# Power-V1_0.net
KiCad netlist of a schematic drawn in Altium Designer
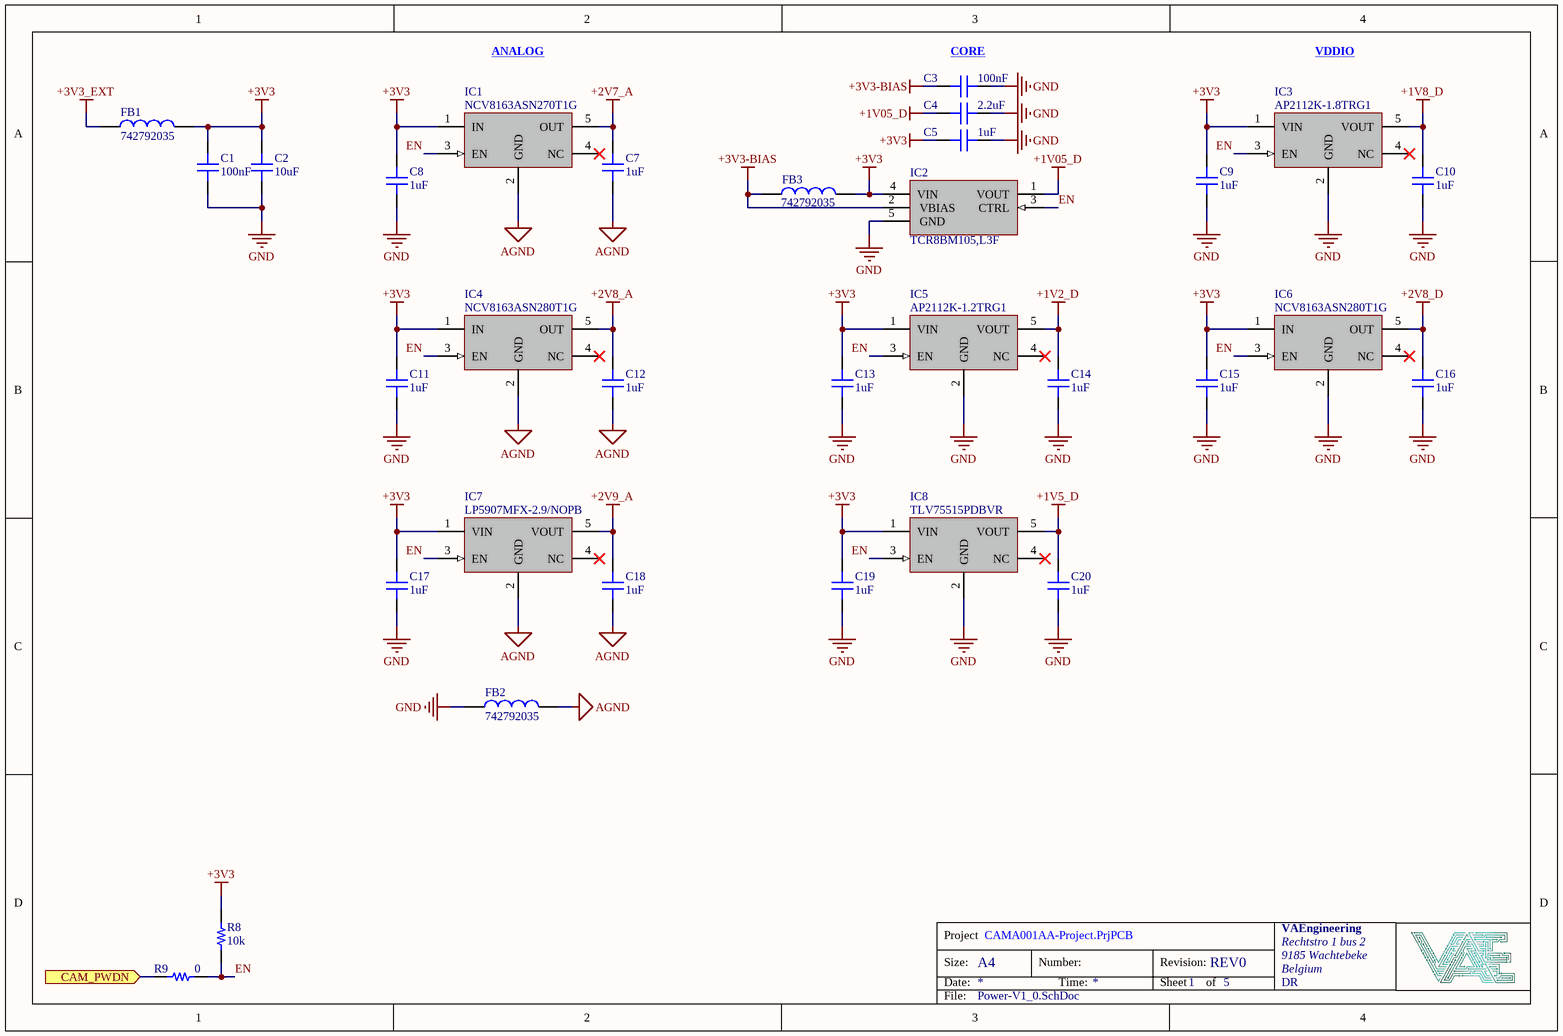
[diagram p0: Power-V1_0.SchDoc]

(export (version "E")
  (design (tool "Eeschema 10.0.6"))
  (components
    (comp (ref "C1")
      (value "CL10B104KB8NNNL")
      (footprint "Esmart C0603")
      (description "CL10 Series 0603 0.1 uF 50 V ±10% Tolerance X7R Multilayer Ceramic Capacitor")
      (fields
        (field (name "MANUFACTURER") "Samsung")
        (field (name "TOLERANCE") "10%")
        (field (name "CAPACITANCE") "100nF")
      )
      (libsource (lib "Passives") (part "Samsung CL10B104KB8NNNL"))
    )
    (comp (ref "C2")
      (value "CL21A106KOQNNWE")
      (footprint "ESmart C0805")
      (description "CAP CER 10UF 16V X5R 0805")
      (fields
        (field (name "MANUFACTURER") "Samsung")
        (field (name "TOLERANCE") "10%")
        (field (name "CAPACITANCE") "10uF")
      )
      (libsource (lib "Passives") (part "Sasmung CL21A106KOQNNWE"))
    )
    (comp (ref "C3")
      (value "CL10B104KB8NNNL")
      (footprint "Esmart C0603")
      (description "CL10 Series 0603 0.1 uF 50 V ±10% Tolerance X7R Multilayer Ceramic Capacitor")
      (fields
        (field (name "MANUFACTURER") "Samsung")
        (field (name "TOLERANCE") "10%")
        (field (name "CAPACITANCE") "100nF")
      )
      (libsource (lib "Passives") (part "Samsung CL10B104KB8NNNL"))
    )
    (comp (ref "C4")
      (value "LMK107B7225KA-TR")
      (footprint "ESMART C0603")
      (description "0603 2.2 uF 10 V ±10 % Tolerance X7R Surface Mount Multilayer Ceramic Capacitor")
      (fields
        (field (name "MANUFACTURER") "Taiyo Yuden")
        (field (name "TOLERANCE") "10%")
        (field (name "CAPACITANCE") "2.2uF")
      )
      (libsource (lib "Passives") (part "Taiyo Yuden LMK107B7225KA-TR"))
    )
    (comp (ref "C5")
      (value "CL10A105KB8NNNC")
      (footprint "ESmart C0603 - Samsung")
      (description "Cap Ceramic 1uF 50V X5R 10% SMD 0603 85C Cardboard T/R")
      (fields
        (field (name "MANUFACTURER") "Samsung")
        (field (name "TOLERANCE") "10%")
        (field (name "CAPACITANCE") "1uF")
      )
      (libsource (lib "Passives") (part "Samsung CL10A105KB8NNNC"))
    )
    (comp (ref "C7")
      (value "CL10A105KB8NNNC")
      (footprint "ESmart C0603 - Samsung")
      (description "Cap Ceramic 1uF 50V X5R 10% SMD 0603 85C Cardboard T/R")
      (fields
        (field (name "MANUFACTURER") "Samsung")
        (field (name "TOLERANCE") "10%")
        (field (name "CAPACITANCE") "1uF")
      )
      (libsource (lib "Passives") (part "Samsung CL10A105KB8NNNC"))
    )
    (comp (ref "C8")
      (value "CL10A105KB8NNNC")
      (footprint "ESmart C0603 - Samsung")
      (description "Cap Ceramic 1uF 50V X5R 10% SMD 0603 85C Cardboard T/R")
      (fields
        (field (name "MANUFACTURER") "Samsung")
        (field (name "TOLERANCE") "10%")
        (field (name "CAPACITANCE") "1uF")
      )
      (libsource (lib "Passives") (part "Samsung CL10A105KB8NNNC"))
    )
    (comp (ref "C9")
      (value "CL10A105KB8NNNC")
      (footprint "ESmart C0603 - Samsung")
      (description "Cap Ceramic 1uF 50V X5R 10% SMD 0603 85C Cardboard T/R")
      (fields
        (field (name "MANUFACTURER") "Samsung")
        (field (name "TOLERANCE") "10%")
        (field (name "CAPACITANCE") "1uF")
      )
      (libsource (lib "Passives") (part "Samsung CL10A105KB8NNNC"))
    )
    (comp (ref "C10")
      (value "CL10A105KB8NNNC")
      (footprint "ESmart C0603 - Samsung")
      (description "Cap Ceramic 1uF 50V X5R 10% SMD 0603 85C Cardboard T/R")
      (fields
        (field (name "MANUFACTURER") "Samsung")
        (field (name "TOLERANCE") "10%")
        (field (name "CAPACITANCE") "1uF")
      )
      (libsource (lib "Passives") (part "Samsung CL10A105KB8NNNC"))
    )
    (comp (ref "C11")
      (value "CL10A105KB8NNNC")
      (footprint "ESmart C0603 - Samsung")
      (description "Cap Ceramic 1uF 50V X5R 10% SMD 0603 85C Cardboard T/R")
      (fields
        (field (name "MANUFACTURER") "Samsung")
        (field (name "TOLERANCE") "10%")
        (field (name "CAPACITANCE") "1uF")
      )
      (libsource (lib "Passives") (part "Samsung CL10A105KB8NNNC"))
    )
    (comp (ref "C12")
      (value "CL10A105KB8NNNC")
      (footprint "ESmart C0603 - Samsung")
      (description "Cap Ceramic 1uF 50V X5R 10% SMD 0603 85C Cardboard T/R")
      (fields
        (field (name "MANUFACTURER") "Samsung")
        (field (name "TOLERANCE") "10%")
        (field (name "CAPACITANCE") "1uF")
      )
      (libsource (lib "Passives") (part "Samsung CL10A105KB8NNNC"))
    )
    (comp (ref "C13")
      (value "CL10A105KB8NNNC")
      (footprint "ESmart C0603 - Samsung")
      (description "Cap Ceramic 1uF 50V X5R 10% SMD 0603 85C Cardboard T/R")
      (fields
        (field (name "MANUFACTURER") "Samsung")
        (field (name "TOLERANCE") "10%")
        (field (name "CAPACITANCE") "1uF")
      )
      (libsource (lib "Passives") (part "Samsung CL10A105KB8NNNC"))
    )
    (comp (ref "C14")
      (value "CL10A105KB8NNNC")
      (footprint "ESmart C0603 - Samsung")
      (description "Cap Ceramic 1uF 50V X5R 10% SMD 0603 85C Cardboard T/R")
      (fields
        (field (name "MANUFACTURER") "Samsung")
        (field (name "TOLERANCE") "10%")
        (field (name "CAPACITANCE") "1uF")
      )
      (libsource (lib "Passives") (part "Samsung CL10A105KB8NNNC"))
    )
    (comp (ref "C15")
      (value "CL10A105KB8NNNC")
      (footprint "ESmart C0603 - Samsung")
      (description "Cap Ceramic 1uF 50V X5R 10% SMD 0603 85C Cardboard T/R")
      (fields
        (field (name "MANUFACTURER") "Samsung")
        (field (name "TOLERANCE") "10%")
        (field (name "CAPACITANCE") "1uF")
      )
      (libsource (lib "Passives") (part "Samsung CL10A105KB8NNNC"))
    )
    (comp (ref "C16")
      (value "CL10A105KB8NNNC")
      (footprint "ESmart C0603 - Samsung")
      (description "Cap Ceramic 1uF 50V X5R 10% SMD 0603 85C Cardboard T/R")
      (fields
        (field (name "MANUFACTURER") "Samsung")
        (field (name "TOLERANCE") "10%")
        (field (name "CAPACITANCE") "1uF")
      )
      (libsource (lib "Passives") (part "Samsung CL10A105KB8NNNC"))
    )
    (comp (ref "C17")
      (value "CL10A105KB8NNNC")
      (footprint "ESmart C0603 - Samsung")
      (description "Cap Ceramic 1uF 50V X5R 10% SMD 0603 85C Cardboard T/R")
      (fields
        (field (name "MANUFACTURER") "Samsung")
        (field (name "TOLERANCE") "10%")
        (field (name "CAPACITANCE") "1uF")
      )
      (libsource (lib "Passives") (part "Samsung CL10A105KB8NNNC"))
    )
    (comp (ref "C18")
      (value "CL10A105KB8NNNC")
      (footprint "ESmart C0603 - Samsung")
      (description "Cap Ceramic 1uF 50V X5R 10% SMD 0603 85C Cardboard T/R")
      (fields
        (field (name "MANUFACTURER") "Samsung")
        (field (name "TOLERANCE") "10%")
        (field (name "CAPACITANCE") "1uF")
      )
      (libsource (lib "Passives") (part "Samsung CL10A105KB8NNNC"))
    )
    (comp (ref "C19")
      (value "CL10A105KB8NNNC")
      (footprint "ESmart C0603 - Samsung")
      (description "Cap Ceramic 1uF 50V X5R 10% SMD 0603 85C Cardboard T/R")
      (fields
        (field (name "MANUFACTURER") "Samsung")
        (field (name "TOLERANCE") "10%")
        (field (name "CAPACITANCE") "1uF")
      )
      (libsource (lib "Passives") (part "Samsung CL10A105KB8NNNC"))
    )
    (comp (ref "C20")
      (value "CL10A105KB8NNNC")
      (footprint "ESmart C0603 - Samsung")
      (description "Cap Ceramic 1uF 50V X5R 10% SMD 0603 85C Cardboard T/R")
      (fields
        (field (name "MANUFACTURER") "Samsung")
        (field (name "TOLERANCE") "10%")
        (field (name "CAPACITANCE") "1uF")
      )
      (libsource (lib "Passives") (part "Samsung CL10A105KB8NNNC"))
    )
    (comp (ref "FB1")
      (value "742792035")
      (footprint "Wurth WE-CBF_0805_High Speed")
      (description "Ferrite Beads WE-CBF 0805 220MHz 300Ohm 300mA")
      (fields (field (name "MANUFACTURER") "Wurth Electronics") (field (name "TOLERANCE") "25%"))
      (libsource (lib "") (part "Wurth 742792035_1"))
    )
    (comp (ref "FB2")
      (value "742792035")
      (footprint "Wurth WE-CBF_0805_High Speed")
      (description "Ferrite Beads WE-CBF 0805 220MHz 300Ohm 300mA")
      (fields (field (name "MANUFACTURER") "Wurth Electronics") (field (name "TOLERANCE") "25%"))
      (libsource (lib "Passives") (part "Wurth 742792035"))
    )
    (comp (ref "FB3")
      (value "742792035")
      (footprint "Wurth WE-CBF_0805_High Speed")
      (description "Ferrite Beads WE-CBF 0805 220MHz 300Ohm 300mA")
      (fields (field (name "MANUFACTURER") "Wurth Electronics") (field (name "TOLERANCE") "25%"))
      (libsource (lib "") (part "Wurth 742792035_1"))
    )
    (comp (ref "IC1")
      (value "NCV8163ASN270T1G")
      (footprint "ON Semi TSOP-5 / CASE 483 / ISSUE M")
      (description "LDO Regulator Pos 2.7V 0.25A Automotive 5-Pin TSOP T/R")
      (fields (field (name "MANUFACTURER") "ON Semiconductor"))
      (libsource (lib "Voltage Regulators Linear") (part "ON Semi NCV8163ASN270T1G"))
    )
    (comp (ref "IC2")
      (value "TCR8BM105,L3F")
      (footprint "Toshiba DFN5B")
      (description "Low Drop-Out Regulator Positive 1.05V 800mA 5-Pin DFN-B")
      (fields (field (name "MANUFACTURER") "Toshiba"))
      (libsource (lib "Voltage Regulators Linear") (part "Toshiba TCR8BM105,L3F"))
    )
    (comp (ref "IC3")
      (value "AP2112K-1.8TRG1")
      (footprint "DIODES SOT-25")
      (description "LDO Regulator Pos 1.8V 0.6A 5-Pin SOT-23 T/R")
      (fields (field (name "MANUFACTURER") "Diodes"))
      (libsource (lib "Voltage Regulators Linear") (part "Diodes AP2112K-1.8TRG1"))
    )
    (comp (ref "IC4")
      (value "NCV8163ASN280T1G")
      (footprint "ON Semi TSOP-5 / CASE 483 / ISSUE M")
      (description "LDO Regulator Pos 2.8V 0.25A Automotive 5-Pin TSOP T/R")
      (fields (field (name "MANUFACTURER") "ON Semiconductor"))
      (libsource (lib "Voltage Regulators Linear") (part "ON Semi NCV8163ASN280T1G"))
    )
    (comp (ref "IC5")
      (value "AP2112K-1.2TRG1")
      (footprint "DIODES SOT-23-5 W5")
      (description "LDO Regulator Pos 1.2V 0.6A 5-Pin SOT-23 T/R")
      (fields (field (name "MANUFACTURER") "Diodes"))
      (libsource (lib "Voltage Regulators Linear") (part "Diodes AP2112K-1.2TRG1"))
    )
    (comp (ref "IC6")
      (value "NCV8163ASN280T1G")
      (footprint "ON Semi TSOP-5 / CASE 483 / ISSUE M")
      (description "LDO Regulator Pos 2.8V 0.25A Automotive 5-Pin TSOP T/R")
      (fields (field (name "MANUFACTURER") "ON Semiconductor"))
      (libsource (lib "Voltage Regulators Linear") (part "ON Semi NCV8163ASN280T1G"))
    )
    (comp (ref "IC7")
      (value "LP5907MFX-2.9/NOPB")
      (footprint "TI SOT-23-5 / DBV0005A")
      (description "LDO Regulator Pos 2.9V 0.25A 5-Pin SOT-23 T/R")
      (fields (field (name "MANUFACTURER") "Texas Instruments"))
      (libsource (lib "Voltage Regulators Linear") (part "TI LP5907MFX-2.9/NOPB"))
    )
    (comp (ref "IC8")
      (value "TLV75515PDBVR")
      (footprint "TI SOT-23-5 / DBV0005A")
      (description "500-mA, high-PSRR, low-IQ, low-dropout voltage regulator with enable 5-SOT-23 -40 to 125")
      (fields (field (name "MANUFACTURER") "Texas Instruments"))
      (libsource (lib "Voltage Regulators Linear") (part "TI TLV75515PDBVR"))
    )
    (comp (ref "R8")
      (value "RMCF0603FT10K0")
      (footprint "ESmart R0603")
      (description "Res Thick Film 0603 10K Ohm 1% 0.1W(1/10W) ±100ppm/C Molded SMD Automotive T/R")
      (fields
        (field (name "MANUFACTURER") "Stackpole Electronics")
        (field (name "TOLERANCE") "1%")
        (field (name "RESISTANCE") "10k")
      )
      (libsource (lib "Passives") (part "Stackpole RMCF0603FT10K0"))
    )
    (comp (ref "R9")
      (value "RMCF0603ZT0R00")
      (footprint "ESmart R0603")
      (description "Res Thkflm 0603 0 Ohm Jumper 1/10W 100Ppm/ C Smd Rohs Compliant: Yes")
      (fields (field (name "MANUFACTURER") "Stackpole Electronics") (field (name "RESISTANCE") "0"))
      (libsource (lib "Passives") (part "Stackpole RMCF0603ZT0R00"))
    )
  )
  (nets
    (net (code "1") (name "+1V2_D") (class "Default")
      (node (ref "C14") (pin "1") (pinfunction "1_1") (pintype "passive"))
      (node (ref "IC5") (pin "5") (pinfunction "VOUT_5") (pintype "power_in"))
    )
    (net (code "2") (name "+1V5_D") (class "Default")
      (node (ref "C20") (pin "1") (pinfunction "1_1") (pintype "passive"))
      (node (ref "IC8") (pin "5") (pinfunction "VOUT_5") (pintype "power_in"))
    )
    (net (code "3") (name "+1V05_D") (class "Default")
      (node (ref "C4") (pin "1") (pinfunction "1_1") (pintype "passive"))
      (node (ref "IC2") (pin "1") (pinfunction "VOUT_1") (pintype "power_in"))
    )
    (net (code "4") (name "+1V8_D") (class "Default")
      (node (ref "C10") (pin "1") (pinfunction "1_1") (pintype "passive"))
      (node (ref "IC3") (pin "5") (pinfunction "VOUT_5") (pintype "power_in"))
    )
    (net (code "5") (name "+2V7_A") (class "Default")
      (node (ref "C7") (pin "1") (pinfunction "1_1") (pintype "passive"))
      (node (ref "IC1") (pin "5") (pinfunction "OUT_5") (pintype "power_in"))
    )
    (net (code "6") (name "+2V8_A") (class "Default")
      (node (ref "C12") (pin "1") (pinfunction "1_1") (pintype "passive"))
      (node (ref "IC4") (pin "5") (pinfunction "OUT_5") (pintype "power_in"))
    )
    (net (code "7") (name "+2V8_D") (class "Default")
      (node (ref "C16") (pin "1") (pinfunction "1_1") (pintype "passive"))
      (node (ref "IC6") (pin "5") (pinfunction "OUT_5") (pintype "power_in"))
    )
    (net (code "8") (name "+2V9_A") (class "Default")
      (node (ref "C18") (pin "1") (pinfunction "1_1") (pintype "passive"))
      (node (ref "IC7") (pin "5") (pinfunction "VOUT_5") (pintype "power_in"))
    )
    (net (code "9") (name "+3V3") (class "Default")
      (node (ref "C1") (pin "2") (pinfunction "2_2") (pintype "passive"))
      (node (ref "C11") (pin "1") (pinfunction "1_1") (pintype "passive"))
      (node (ref "C13") (pin "1") (pinfunction "1_1") (pintype "passive"))
      (node (ref "C15") (pin "1") (pinfunction "1_1") (pintype "passive"))
      (node (ref "C17") (pin "1") (pinfunction "1_1") (pintype "passive"))
      (node (ref "C19") (pin "1") (pinfunction "1_1") (pintype "passive"))
      (node (ref "C2") (pin "2") (pinfunction "2_2") (pintype "passive"))
      (node (ref "C5") (pin "1") (pinfunction "1_1") (pintype "passive"))
      (node (ref "C8") (pin "1") (pinfunction "1_1") (pintype "passive"))
      (node (ref "C9") (pin "1") (pinfunction "1_1") (pintype "passive"))
      (node (ref "FB1") (pin "1") (pinfunction "1_1") (pintype "passive"))
      (node (ref "FB3") (pin "1") (pinfunction "1_1") (pintype "passive"))
      (node (ref "IC1") (pin "1") (pinfunction "IN_1") (pintype "power_in"))
      (node (ref "IC2") (pin "4") (pinfunction "VIN_4") (pintype "power_in"))
      (node (ref "IC3") (pin "1") (pinfunction "VIN_1") (pintype "power_in"))
      (node (ref "IC4") (pin "1") (pinfunction "IN_1") (pintype "power_in"))
      (node (ref "IC5") (pin "1") (pinfunction "VIN_1") (pintype "power_in"))
      (node (ref "IC6") (pin "1") (pinfunction "IN_1") (pintype "power_in"))
      (node (ref "IC7") (pin "1") (pinfunction "VIN_1") (pintype "power_in"))
      (node (ref "IC8") (pin "1") (pinfunction "VIN_1") (pintype "power_in"))
      (node (ref "R8") (pin "1") (pinfunction "1_1") (pintype "passive"))
    )
    (net (code "10") (name "+3V3-BIAS") (class "Default")
      (node (ref "C3") (pin "1") (pinfunction "1_1") (pintype "passive"))
      (node (ref "FB3") (pin "2") (pinfunction "2_2") (pintype "passive"))
      (node (ref "IC2") (pin "2") (pinfunction "VBIAS_2") (pintype "power_in"))
    )
    (net (code "11") (name "+3V3_EXT") (class "Default")
      (node (ref "FB1") (pin "2") (pinfunction "2_2") (pintype "passive"))
    )
    (net (code "12") (name "/CAM_PWDN") (class "Default")
      (node (ref "R9") (pin "1") (pinfunction "1_1") (pintype "passive"))
    )
    (net (code "13") (name "/EN") (class "Default")
      (node (ref "IC1") (pin "3") (pinfunction "EN_3") (pintype "input"))
      (node (ref "IC2") (pin "3") (pinfunction "CTRL_3") (pintype "input"))
      (node (ref "IC3") (pin "3") (pinfunction "EN_3") (pintype "input"))
      (node (ref "IC4") (pin "3") (pinfunction "EN_3") (pintype "input"))
      (node (ref "IC5") (pin "3") (pinfunction "EN_3") (pintype "input"))
      (node (ref "IC6") (pin "3") (pinfunction "EN_3") (pintype "input"))
      (node (ref "IC7") (pin "3") (pinfunction "EN_3") (pintype "input"))
      (node (ref "IC8") (pin "3") (pinfunction "EN_3") (pintype "input"))
      (node (ref "R8") (pin "2") (pinfunction "2_2") (pintype "passive"))
      (node (ref "R9") (pin "2") (pinfunction "2_2") (pintype "passive"))
    )
    (net (code "14") (name "AGND") (class "Default")
      (node (ref "C12") (pin "2") (pinfunction "2_2") (pintype "passive"))
      (node (ref "C18") (pin "2") (pinfunction "2_2") (pintype "passive"))
      (node (ref "C7") (pin "2") (pinfunction "2_2") (pintype "passive"))
      (node (ref "FB2") (pin "2") (pinfunction "2_2") (pintype "passive"))
      (node (ref "IC1") (pin "2") (pinfunction "GND_2") (pintype "power_in"))
      (node (ref "IC4") (pin "2") (pinfunction "GND_2") (pintype "power_in"))
      (node (ref "IC7") (pin "2") (pinfunction "GND_2") (pintype "power_in"))
    )
    (net (code "15") (name "GND") (class "Default")
      (node (ref "C1") (pin "1") (pinfunction "1_1") (pintype "passive"))
      (node (ref "C10") (pin "2") (pinfunction "2_2") (pintype "passive"))
      (node (ref "C11") (pin "2") (pinfunction "2_2") (pintype "passive"))
      (node (ref "C13") (pin "2") (pinfunction "2_2") (pintype "passive"))
      (node (ref "C14") (pin "2") (pinfunction "2_2") (pintype "passive"))
      (node (ref "C15") (pin "2") (pinfunction "2_2") (pintype "passive"))
      (node (ref "C16") (pin "2") (pinfunction "2_2") (pintype "passive"))
      (node (ref "C17") (pin "2") (pinfunction "2_2") (pintype "passive"))
      (node (ref "C19") (pin "2") (pinfunction "2_2") (pintype "passive"))
      (node (ref "C2") (pin "1") (pinfunction "1_1") (pintype "passive"))
      (node (ref "C20") (pin "2") (pinfunction "2_2") (pintype "passive"))
      (node (ref "C3") (pin "2") (pinfunction "2_2") (pintype "passive"))
      (node (ref "C4") (pin "2") (pinfunction "2_2") (pintype "passive"))
      (node (ref "C5") (pin "2") (pinfunction "2_2") (pintype "passive"))
      (node (ref "C8") (pin "2") (pinfunction "2_2") (pintype "passive"))
      (node (ref "C9") (pin "2") (pinfunction "2_2") (pintype "passive"))
      (node (ref "FB2") (pin "1") (pinfunction "1_1") (pintype "passive"))
      (node (ref "IC2") (pin "5") (pinfunction "GND_5") (pintype "power_in"))
      (node (ref "IC3") (pin "2") (pinfunction "GND_2") (pintype "power_in"))
      (node (ref "IC5") (pin "2") (pinfunction "GND_2") (pintype "power_in"))
      (node (ref "IC6") (pin "2") (pinfunction "GND_2") (pintype "power_in"))
      (node (ref "IC8") (pin "2") (pinfunction "GND_2") (pintype "power_in"))
    )
    (net (code "16") (name "unconnected-(IC1-NC-Pad4)") (class "Default")
      (node (ref "IC1") (pin "4") (pinfunction "NC_4") (pintype "passive+no_connect"))
    )
    (net (code "17") (name "unconnected-(IC3-NC-Pad4)") (class "Default")
      (node (ref "IC3") (pin "4") (pinfunction "NC_4") (pintype "passive+no_connect"))
    )
    (net (code "18") (name "unconnected-(IC4-NC-Pad4)") (class "Default")
      (node (ref "IC4") (pin "4") (pinfunction "NC_4") (pintype "passive+no_connect"))
    )
    (net (code "19") (name "unconnected-(IC5-NC-Pad4)") (class "Default")
      (node (ref "IC5") (pin "4") (pinfunction "NC_4") (pintype "passive+no_connect"))
    )
    (net (code "20") (name "unconnected-(IC6-NC-Pad4)") (class "Default")
      (node (ref "IC6") (pin "4") (pinfunction "NC_4") (pintype "passive+no_connect"))
    )
    (net (code "21") (name "unconnected-(IC7-NC-Pad4)") (class "Default")
      (node (ref "IC7") (pin "4") (pinfunction "NC_4") (pintype "passive+no_connect"))
    )
    (net (code "22") (name "unconnected-(IC8-NC-Pad4)") (class "Default")
      (node (ref "IC8") (pin "4") (pinfunction "NC_4") (pintype "passive+no_connect"))
    )
  )
)
